# 004.net
KiCad netlist of a schematic drawn in EAGLE
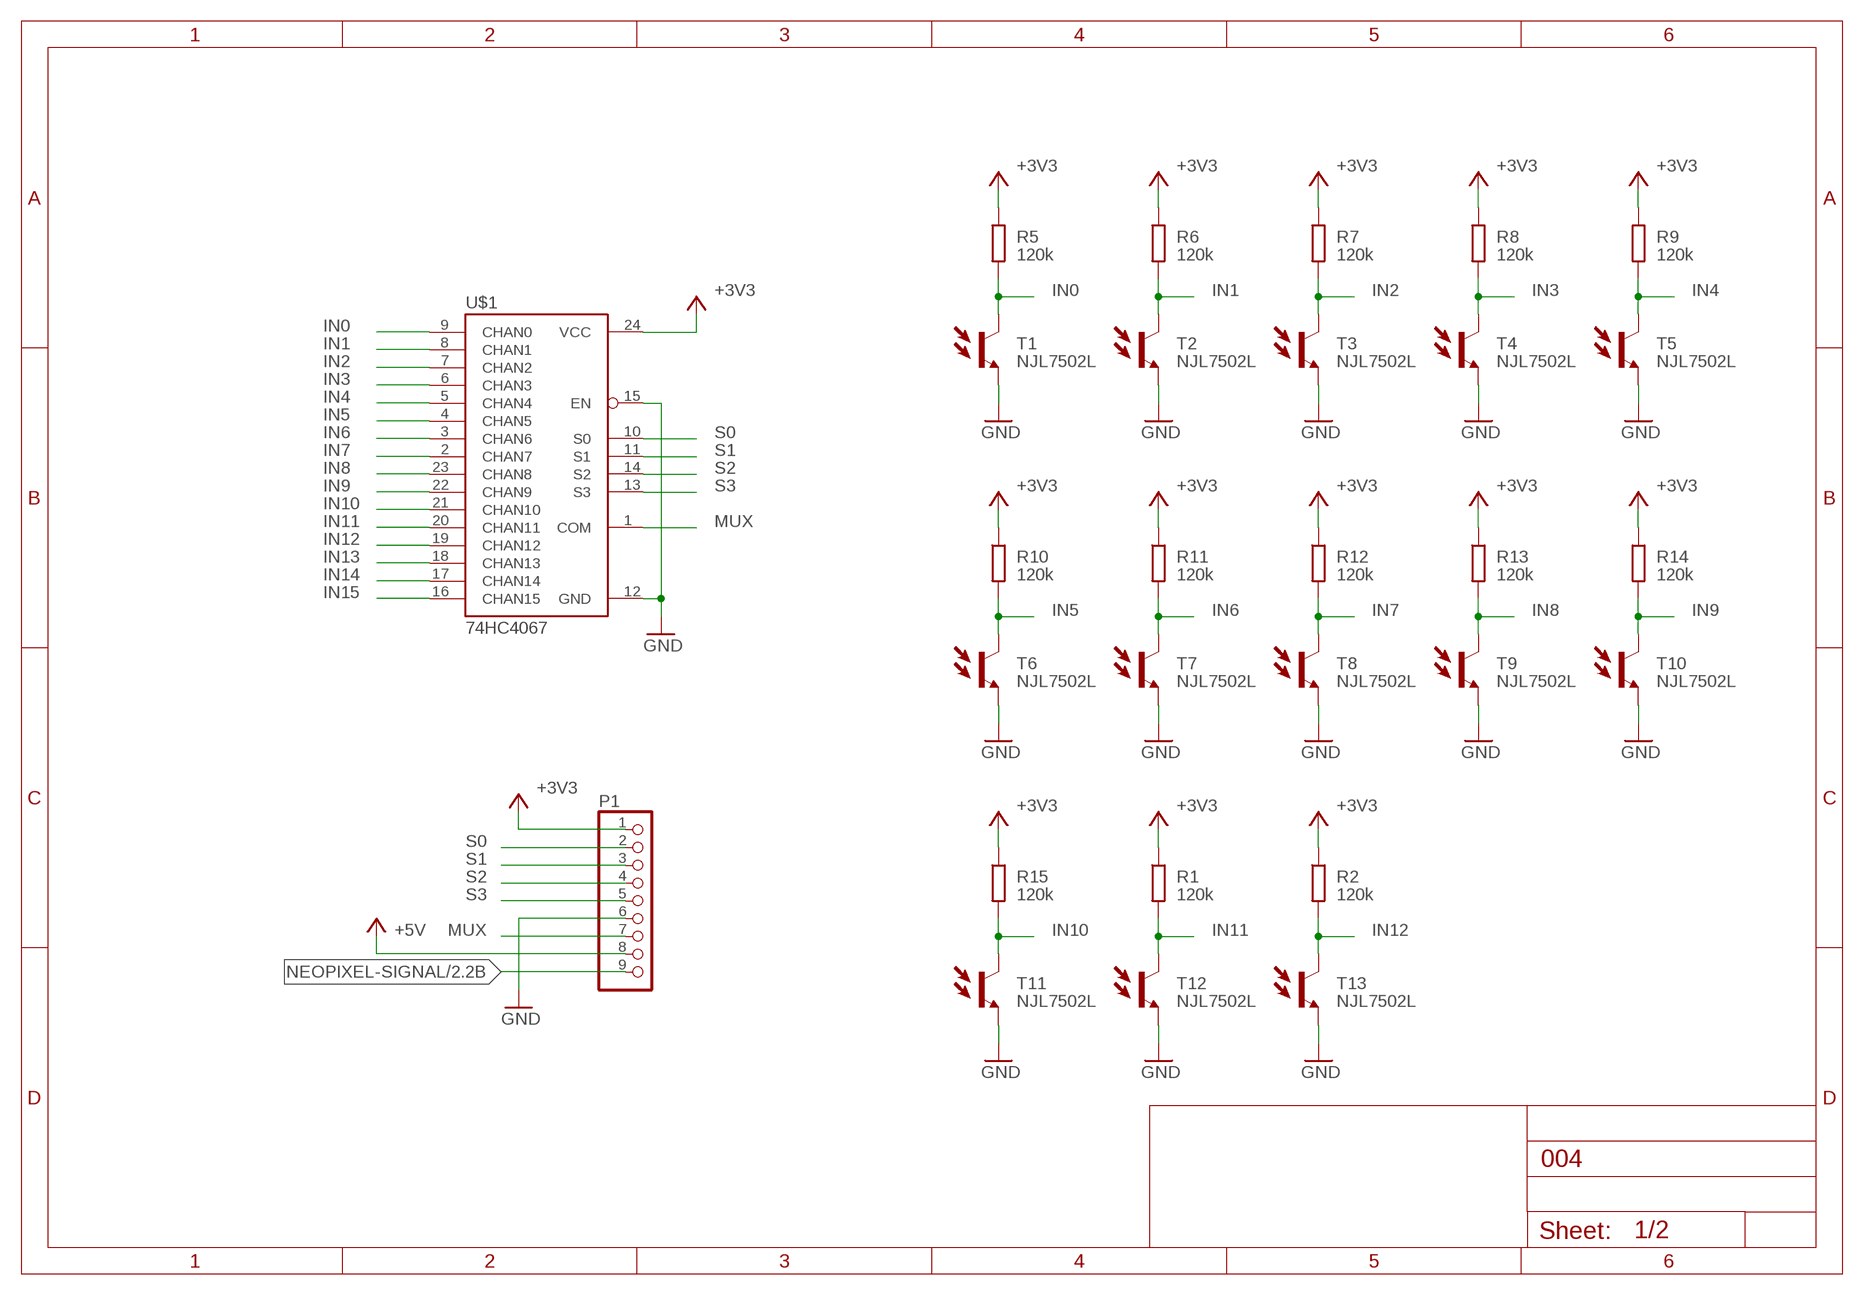
[diagram p0: schematic, sheet 1]
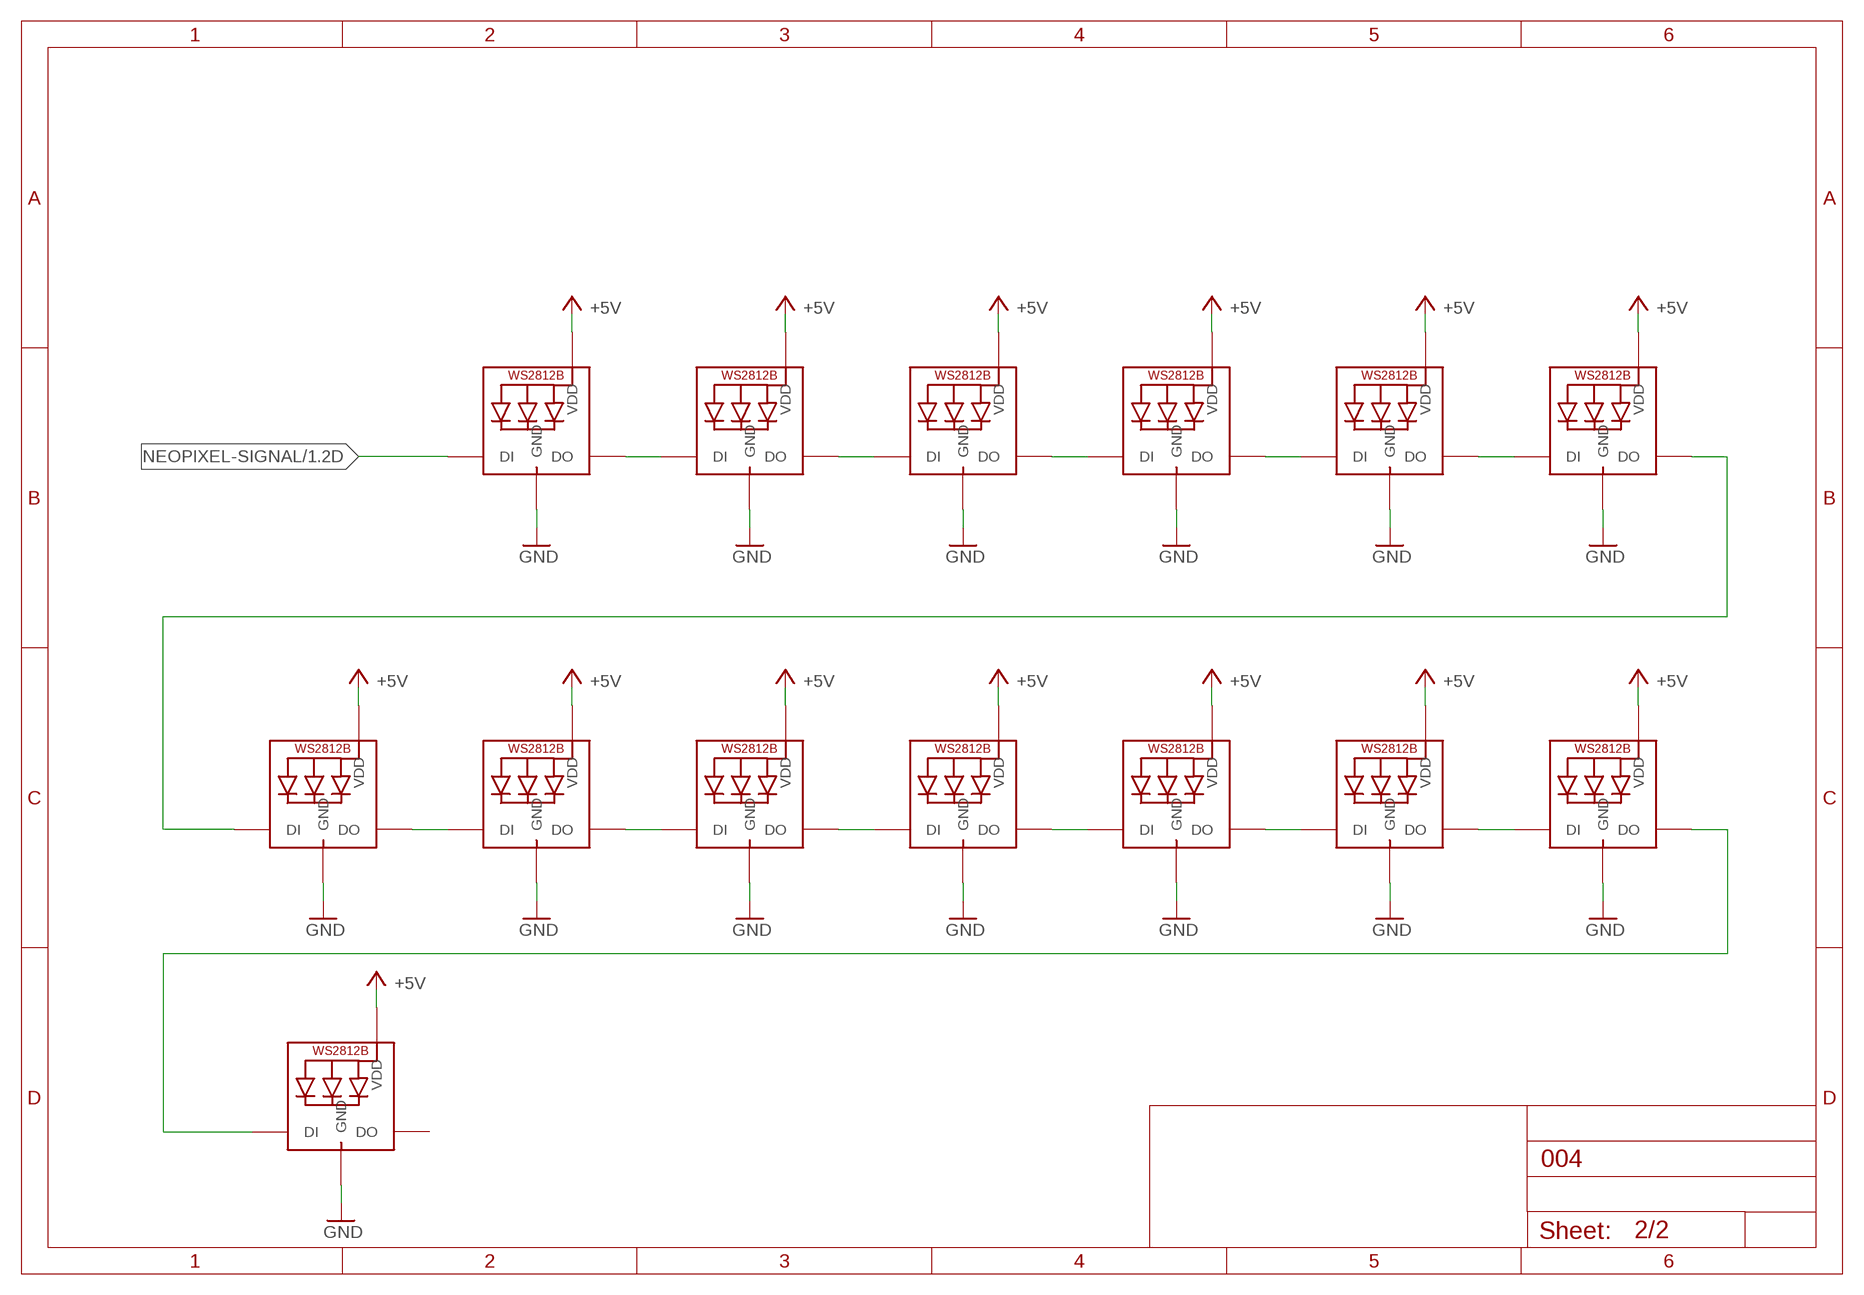
[diagram p1: schematic, sheet 2]

(export (version "E")
  (design (tool "Eeschema 10.0.6"))
  (components
    (comp (ref "P1")
      (value "S9B-ZR-SM4A-TF")
      (footprint "eagle-import:ZH-SM4-SIDE09")
      (libsource (lib "eagle-import") (part "S9B-ZR-SM4A-TF"))
    )
    (comp (ref "R1")
      (value "120k")
      (footprint "eagle-import:R0805")
      (libsource (lib "eagle-import") (part "R-EU_R0805"))
    )
    (comp (ref "R2")
      (value "120k")
      (footprint "eagle-import:R0805")
      (libsource (lib "eagle-import") (part "R-EU_R0805"))
    )
    (comp (ref "R5")
      (value "120k")
      (footprint "eagle-import:R0805")
      (libsource (lib "eagle-import") (part "R-EU_R0805"))
    )
    (comp (ref "R6")
      (value "120k")
      (footprint "eagle-import:R0805")
      (libsource (lib "eagle-import") (part "R-EU_R0805"))
    )
    (comp (ref "R7")
      (value "120k")
      (footprint "eagle-import:R0805")
      (libsource (lib "eagle-import") (part "R-EU_R0805"))
    )
    (comp (ref "R8")
      (value "120k")
      (footprint "eagle-import:R0805")
      (libsource (lib "eagle-import") (part "R-EU_R0805"))
    )
    (comp (ref "R9")
      (value "120k")
      (footprint "eagle-import:R0805")
      (libsource (lib "eagle-import") (part "R-EU_R0805"))
    )
    (comp (ref "R10")
      (value "120k")
      (footprint "eagle-import:R0805")
      (libsource (lib "eagle-import") (part "R-EU_R0805"))
    )
    (comp (ref "R11")
      (value "120k")
      (footprint "eagle-import:R0805")
      (libsource (lib "eagle-import") (part "R-EU_R0805"))
    )
    (comp (ref "R12")
      (value "120k")
      (footprint "eagle-import:R0805")
      (libsource (lib "eagle-import") (part "R-EU_R0805"))
    )
    (comp (ref "R13")
      (value "120k")
      (footprint "eagle-import:R0805")
      (libsource (lib "eagle-import") (part "R-EU_R0805"))
    )
    (comp (ref "R14")
      (value "120k")
      (footprint "eagle-import:R0805")
      (libsource (lib "eagle-import") (part "R-EU_R0805"))
    )
    (comp (ref "R15")
      (value "120k")
      (footprint "eagle-import:R0805")
      (libsource (lib "eagle-import") (part "R-EU_R0805"))
    )
    (comp (ref "T1")
      (value "NJL7502L")
      (footprint "eagle-import:MYPARTS_NJL7502L")
      (libsource (lib "eagle-import") (part "MYPARTS_NJL7502L"))
    )
    (comp (ref "T2")
      (value "NJL7502L")
      (footprint "eagle-import:MYPARTS_NJL7502L")
      (libsource (lib "eagle-import") (part "MYPARTS_NJL7502L"))
    )
    (comp (ref "T3")
      (value "NJL7502L")
      (footprint "eagle-import:MYPARTS_NJL7502L")
      (libsource (lib "eagle-import") (part "MYPARTS_NJL7502L"))
    )
    (comp (ref "T4")
      (value "NJL7502L")
      (footprint "eagle-import:MYPARTS_NJL7502L")
      (libsource (lib "eagle-import") (part "MYPARTS_NJL7502L"))
    )
    (comp (ref "T5")
      (value "NJL7502L")
      (footprint "eagle-import:MYPARTS_NJL7502L")
      (libsource (lib "eagle-import") (part "MYPARTS_NJL7502L"))
    )
    (comp (ref "T6")
      (value "NJL7502L")
      (footprint "eagle-import:MYPARTS_NJL7502L")
      (libsource (lib "eagle-import") (part "MYPARTS_NJL7502L"))
    )
    (comp (ref "T7")
      (value "NJL7502L")
      (footprint "eagle-import:MYPARTS_NJL7502L")
      (libsource (lib "eagle-import") (part "MYPARTS_NJL7502L"))
    )
    (comp (ref "T8")
      (value "NJL7502L")
      (footprint "eagle-import:MYPARTS_NJL7502L")
      (libsource (lib "eagle-import") (part "MYPARTS_NJL7502L"))
    )
    (comp (ref "T9")
      (value "NJL7502L")
      (footprint "eagle-import:MYPARTS_NJL7502L")
      (libsource (lib "eagle-import") (part "MYPARTS_NJL7502L"))
    )
    (comp (ref "T10")
      (value "NJL7502L")
      (footprint "eagle-import:MYPARTS_NJL7502L")
      (libsource (lib "eagle-import") (part "MYPARTS_NJL7502L"))
    )
    (comp (ref "T11")
      (value "NJL7502L")
      (footprint "eagle-import:MYPARTS_NJL7502L")
      (libsource (lib "eagle-import") (part "MYPARTS_NJL7502L"))
    )
    (comp (ref "T12")
      (value "NJL7502L")
      (footprint "eagle-import:MYPARTS_NJL7502L")
      (libsource (lib "eagle-import") (part "MYPARTS_NJL7502L"))
    )
    (comp (ref "T13")
      (value "NJL7502L")
      (footprint "eagle-import:MYPARTS_NJL7502L")
      (libsource (lib "eagle-import") (part "MYPARTS_NJL7502L"))
    )
    (comp (ref "U$1")
      (value "74HC4067")
      (footprint "eagle-import:SPARKFUN_SSOP24")
      (libsource (lib "eagle-import") (part "SPARKFUN_MUX-74HC4067SMD"))
    )
    (comp (ref "LED1")
      (value "WS2812B5050")
      (footprint "eagle-import:WS2812B")
      (libsource (lib "eagle-import") (part "WS2812B5050"))
    )
    (comp (ref "LED2")
      (value "WS2812B5050")
      (footprint "eagle-import:WS2812B")
      (libsource (lib "eagle-import") (part "WS2812B5050"))
    )
    (comp (ref "LED3")
      (value "WS2812B5050")
      (footprint "eagle-import:WS2812B")
      (libsource (lib "eagle-import") (part "WS2812B5050"))
    )
    (comp (ref "LED4")
      (value "WS2812B5050")
      (footprint "eagle-import:WS2812B")
      (libsource (lib "eagle-import") (part "WS2812B5050"))
    )
    (comp (ref "LED5")
      (value "WS2812B5050")
      (footprint "eagle-import:WS2812B")
      (libsource (lib "eagle-import") (part "WS2812B5050"))
    )
    (comp (ref "LED6")
      (value "WS2812B5050")
      (footprint "eagle-import:WS2812B")
      (libsource (lib "eagle-import") (part "WS2812B5050"))
    )
    (comp (ref "LED7")
      (value "WS2812B5050")
      (footprint "eagle-import:WS2812B")
      (libsource (lib "eagle-import") (part "WS2812B5050"))
    )
    (comp (ref "LED8")
      (value "WS2812B5050")
      (footprint "eagle-import:WS2812B")
      (libsource (lib "eagle-import") (part "WS2812B5050"))
    )
    (comp (ref "LED9")
      (value "WS2812B5050")
      (footprint "eagle-import:WS2812B")
      (libsource (lib "eagle-import") (part "WS2812B5050"))
    )
    (comp (ref "LED10")
      (value "WS2812B5050")
      (footprint "eagle-import:WS2812B")
      (libsource (lib "eagle-import") (part "WS2812B5050"))
    )
    (comp (ref "LED11")
      (value "WS2812B5050")
      (footprint "eagle-import:WS2812B")
      (libsource (lib "eagle-import") (part "WS2812B5050"))
    )
    (comp (ref "LED12")
      (value "WS2812B5050")
      (footprint "eagle-import:WS2812B")
      (libsource (lib "eagle-import") (part "WS2812B5050"))
    )
    (comp (ref "LED13")
      (value "WS2812B5050")
      (footprint "eagle-import:WS2812B")
      (libsource (lib "eagle-import") (part "WS2812B5050"))
    )
    (comp (ref "LED14")
      (value "WS2812B5050")
      (footprint "eagle-import:WS2812B")
      (libsource (lib "eagle-import") (part "WS2812B5050"))
    )
  )
  (nets
    (net (code "1") (name "+3V3") (class "Default")
      (node (ref "P1") (pin "1") (pinfunction "1_1") (pintype "passive"))
      (node (ref "R1") (pin "1") (pinfunction "1_1") (pintype "passive"))
      (node (ref "R10") (pin "1") (pinfunction "1_1") (pintype "passive"))
      (node (ref "R11") (pin "1") (pinfunction "1_1") (pintype "passive"))
      (node (ref "R12") (pin "1") (pinfunction "1_1") (pintype "passive"))
      (node (ref "R13") (pin "1") (pinfunction "1_1") (pintype "passive"))
      (node (ref "R14") (pin "1") (pinfunction "1_1") (pintype "passive"))
      (node (ref "R15") (pin "1") (pinfunction "1_1") (pintype "passive"))
      (node (ref "R2") (pin "1") (pinfunction "1_1") (pintype "passive"))
      (node (ref "R5") (pin "1") (pinfunction "1_1") (pintype "passive"))
      (node (ref "R6") (pin "1") (pinfunction "1_1") (pintype "passive"))
      (node (ref "R7") (pin "1") (pinfunction "1_1") (pintype "passive"))
      (node (ref "R8") (pin "1") (pinfunction "1_1") (pintype "passive"))
      (node (ref "R9") (pin "1") (pinfunction "1_1") (pintype "passive"))
      (node (ref "U$1") (pin "24") (pinfunction "VCC_24") (pintype "bidirectional"))
    )
    (net (code "2") (name "+5V") (class "Default")
      (node (ref "LED1") (pin "1-VDD") (pinfunction "VDD_1-VDD") (pintype "power_in"))
      (node (ref "LED10") (pin "1-VDD") (pinfunction "VDD_1-VDD") (pintype "power_in"))
      (node (ref "LED11") (pin "1-VDD") (pinfunction "VDD_1-VDD") (pintype "power_in"))
      (node (ref "LED12") (pin "1-VDD") (pinfunction "VDD_1-VDD") (pintype "power_in"))
      (node (ref "LED13") (pin "1-VDD") (pinfunction "VDD_1-VDD") (pintype "power_in"))
      (node (ref "LED14") (pin "1-VDD") (pinfunction "VDD_1-VDD") (pintype "power_in"))
      (node (ref "LED2") (pin "1-VDD") (pinfunction "VDD_1-VDD") (pintype "power_in"))
      (node (ref "LED3") (pin "1-VDD") (pinfunction "VDD_1-VDD") (pintype "power_in"))
      (node (ref "LED4") (pin "1-VDD") (pinfunction "VDD_1-VDD") (pintype "power_in"))
      (node (ref "LED5") (pin "1-VDD") (pinfunction "VDD_1-VDD") (pintype "power_in"))
      (node (ref "LED6") (pin "1-VDD") (pinfunction "VDD_1-VDD") (pintype "power_in"))
      (node (ref "LED7") (pin "1-VDD") (pinfunction "VDD_1-VDD") (pintype "power_in"))
      (node (ref "LED8") (pin "1-VDD") (pinfunction "VDD_1-VDD") (pintype "power_in"))
      (node (ref "LED9") (pin "1-VDD") (pinfunction "VDD_1-VDD") (pintype "power_in"))
      (node (ref "P1") (pin "8") (pinfunction "8_8") (pintype "passive"))
    )
    (net (code "3") (name "GND") (class "Default")
      (node (ref "LED1") (pin "3-GND") (pinfunction "GND_3-GND") (pintype "power_in"))
      (node (ref "LED10") (pin "3-GND") (pinfunction "GND_3-GND") (pintype "power_in"))
      (node (ref "LED11") (pin "3-GND") (pinfunction "GND_3-GND") (pintype "power_in"))
      (node (ref "LED12") (pin "3-GND") (pinfunction "GND_3-GND") (pintype "power_in"))
      (node (ref "LED13") (pin "3-GND") (pinfunction "GND_3-GND") (pintype "power_in"))
      (node (ref "LED14") (pin "3-GND") (pinfunction "GND_3-GND") (pintype "power_in"))
      (node (ref "LED2") (pin "3-GND") (pinfunction "GND_3-GND") (pintype "power_in"))
      (node (ref "LED3") (pin "3-GND") (pinfunction "GND_3-GND") (pintype "power_in"))
      (node (ref "LED4") (pin "3-GND") (pinfunction "GND_3-GND") (pintype "power_in"))
      (node (ref "LED5") (pin "3-GND") (pinfunction "GND_3-GND") (pintype "power_in"))
      (node (ref "LED6") (pin "3-GND") (pinfunction "GND_3-GND") (pintype "power_in"))
      (node (ref "LED7") (pin "3-GND") (pinfunction "GND_3-GND") (pintype "power_in"))
      (node (ref "LED8") (pin "3-GND") (pinfunction "GND_3-GND") (pintype "power_in"))
      (node (ref "LED9") (pin "3-GND") (pinfunction "GND_3-GND") (pintype "power_in"))
      (node (ref "P1") (pin "6") (pinfunction "6_6") (pintype "passive"))
      (node (ref "T1") (pin "E") (pinfunction "E_E") (pintype "passive"))
      (node (ref "T10") (pin "E") (pinfunction "E_E") (pintype "passive"))
      (node (ref "T11") (pin "E") (pinfunction "E_E") (pintype "passive"))
      (node (ref "T12") (pin "E") (pinfunction "E_E") (pintype "passive"))
      (node (ref "T13") (pin "E") (pinfunction "E_E") (pintype "passive"))
      (node (ref "T2") (pin "E") (pinfunction "E_E") (pintype "passive"))
      (node (ref "T3") (pin "E") (pinfunction "E_E") (pintype "passive"))
      (node (ref "T4") (pin "E") (pinfunction "E_E") (pintype "passive"))
      (node (ref "T5") (pin "E") (pinfunction "E_E") (pintype "passive"))
      (node (ref "T6") (pin "E") (pinfunction "E_E") (pintype "passive"))
      (node (ref "T7") (pin "E") (pinfunction "E_E") (pintype "passive"))
      (node (ref "T8") (pin "E") (pinfunction "E_E") (pintype "passive"))
      (node (ref "T9") (pin "E") (pinfunction "E_E") (pintype "passive"))
      (node (ref "U$1") (pin "12") (pinfunction "GND_12") (pintype "bidirectional"))
      (node (ref "U$1") (pin "15") (pinfunction "EN_15") (pintype "input"))
    )
    (net (code "4") (name "IN0") (class "Default")
      (node (ref "R5") (pin "2") (pinfunction "2_2") (pintype "passive"))
      (node (ref "T1") (pin "C") (pinfunction "C_C") (pintype "passive"))
      (node (ref "U$1") (pin "9") (pinfunction "CHAN0_9") (pintype "bidirectional"))
    )
    (net (code "5") (name "IN1") (class "Default")
      (node (ref "R6") (pin "2") (pinfunction "2_2") (pintype "passive"))
      (node (ref "T2") (pin "C") (pinfunction "C_C") (pintype "passive"))
      (node (ref "U$1") (pin "8") (pinfunction "CHAN1_8") (pintype "bidirectional"))
    )
    (net (code "6") (name "IN2") (class "Default")
      (node (ref "R7") (pin "2") (pinfunction "2_2") (pintype "passive"))
      (node (ref "T3") (pin "C") (pinfunction "C_C") (pintype "passive"))
      (node (ref "U$1") (pin "7") (pinfunction "CHAN2_7") (pintype "bidirectional"))
    )
    (net (code "7") (name "IN3") (class "Default")
      (node (ref "R8") (pin "2") (pinfunction "2_2") (pintype "passive"))
      (node (ref "T4") (pin "C") (pinfunction "C_C") (pintype "passive"))
      (node (ref "U$1") (pin "6") (pinfunction "CHAN3_6") (pintype "bidirectional"))
    )
    (net (code "8") (name "IN4") (class "Default")
      (node (ref "R9") (pin "2") (pinfunction "2_2") (pintype "passive"))
      (node (ref "T5") (pin "C") (pinfunction "C_C") (pintype "passive"))
      (node (ref "U$1") (pin "5") (pinfunction "CHAN4_5") (pintype "bidirectional"))
    )
    (net (code "9") (name "IN5") (class "Default")
      (node (ref "R10") (pin "2") (pinfunction "2_2") (pintype "passive"))
      (node (ref "T6") (pin "C") (pinfunction "C_C") (pintype "passive"))
      (node (ref "U$1") (pin "4") (pinfunction "CHAN5_4") (pintype "bidirectional"))
    )
    (net (code "10") (name "IN6") (class "Default")
      (node (ref "R11") (pin "2") (pinfunction "2_2") (pintype "passive"))
      (node (ref "T7") (pin "C") (pinfunction "C_C") (pintype "passive"))
      (node (ref "U$1") (pin "3") (pinfunction "CHAN6_3") (pintype "bidirectional"))
    )
    (net (code "11") (name "IN7") (class "Default")
      (node (ref "R12") (pin "2") (pinfunction "2_2") (pintype "passive"))
      (node (ref "T8") (pin "C") (pinfunction "C_C") (pintype "passive"))
      (node (ref "U$1") (pin "2") (pinfunction "CHAN7_2") (pintype "bidirectional"))
    )
    (net (code "12") (name "IN8") (class "Default")
      (node (ref "R13") (pin "2") (pinfunction "2_2") (pintype "passive"))
      (node (ref "T9") (pin "C") (pinfunction "C_C") (pintype "passive"))
      (node (ref "U$1") (pin "23") (pinfunction "CHAN8_23") (pintype "bidirectional"))
    )
    (net (code "13") (name "IN9") (class "Default")
      (node (ref "R14") (pin "2") (pinfunction "2_2") (pintype "passive"))
      (node (ref "T10") (pin "C") (pinfunction "C_C") (pintype "passive"))
      (node (ref "U$1") (pin "22") (pinfunction "CHAN9_22") (pintype "bidirectional"))
    )
    (net (code "14") (name "IN10") (class "Default")
      (node (ref "R15") (pin "2") (pinfunction "2_2") (pintype "passive"))
      (node (ref "T11") (pin "C") (pinfunction "C_C") (pintype "passive"))
      (node (ref "U$1") (pin "21") (pinfunction "CHAN10_21") (pintype "bidirectional"))
    )
    (net (code "15") (name "IN11") (class "Default")
      (node (ref "R1") (pin "2") (pinfunction "2_2") (pintype "passive"))
      (node (ref "T12") (pin "C") (pinfunction "C_C") (pintype "passive"))
      (node (ref "U$1") (pin "20") (pinfunction "CHAN11_20") (pintype "bidirectional"))
    )
    (net (code "16") (name "IN12") (class "Default")
      (node (ref "R2") (pin "2") (pinfunction "2_2") (pintype "passive"))
      (node (ref "T13") (pin "C") (pinfunction "C_C") (pintype "passive"))
      (node (ref "U$1") (pin "19") (pinfunction "CHAN12_19") (pintype "bidirectional"))
    )
    (net (code "17") (name "IN13") (class "Default")
      (node (ref "U$1") (pin "18") (pinfunction "CHAN13_18") (pintype "bidirectional"))
    )
    (net (code "18") (name "IN14") (class "Default")
      (node (ref "U$1") (pin "17") (pinfunction "CHAN14_17") (pintype "bidirectional"))
    )
    (net (code "19") (name "IN15") (class "Default")
      (node (ref "U$1") (pin "16") (pinfunction "CHAN15_16") (pintype "bidirectional"))
    )
    (net (code "20") (name "MUX") (class "Default")
      (node (ref "P1") (pin "7") (pinfunction "7_7") (pintype "passive"))
      (node (ref "U$1") (pin "1") (pinfunction "COM_1") (pintype "bidirectional"))
    )
    (net (code "21") (name "NEOPIXEL-SIGNAL") (class "Default")
      (node (ref "LED1") (pin "4-DIN") (pinfunction "DI_4-DIN") (pintype "input"))
      (node (ref "P1") (pin "9") (pinfunction "9_9") (pintype "passive"))
    )
    (net (code "22") (name "Net-(LED1-DO)") (class "Default")
      (node (ref "LED1") (pin "2-DOUT") (pinfunction "DO_2-DOUT") (pintype "output"))
      (node (ref "LED2") (pin "4-DIN") (pinfunction "DI_4-DIN") (pintype "input"))
    )
    (net (code "23") (name "Net-(LED2-DO)") (class "Default")
      (node (ref "LED2") (pin "2-DOUT") (pinfunction "DO_2-DOUT") (pintype "output"))
      (node (ref "LED3") (pin "4-DIN") (pinfunction "DI_4-DIN") (pintype "input"))
    )
    (net (code "24") (name "Net-(LED3-DO)") (class "Default")
      (node (ref "LED3") (pin "2-DOUT") (pinfunction "DO_2-DOUT") (pintype "output"))
      (node (ref "LED4") (pin "4-DIN") (pinfunction "DI_4-DIN") (pintype "input"))
    )
    (net (code "25") (name "Net-(LED4-DO)") (class "Default")
      (node (ref "LED4") (pin "2-DOUT") (pinfunction "DO_2-DOUT") (pintype "output"))
      (node (ref "LED5") (pin "4-DIN") (pinfunction "DI_4-DIN") (pintype "input"))
    )
    (net (code "26") (name "Net-(LED5-DO)") (class "Default")
      (node (ref "LED5") (pin "2-DOUT") (pinfunction "DO_2-DOUT") (pintype "output"))
      (node (ref "LED6") (pin "4-DIN") (pinfunction "DI_4-DIN") (pintype "input"))
    )
    (net (code "27") (name "Net-(LED6-DO)") (class "Default")
      (node (ref "LED6") (pin "2-DOUT") (pinfunction "DO_2-DOUT") (pintype "output"))
      (node (ref "LED7") (pin "4-DIN") (pinfunction "DI_4-DIN") (pintype "input"))
    )
    (net (code "28") (name "Net-(LED7-DO)") (class "Default")
      (node (ref "LED7") (pin "2-DOUT") (pinfunction "DO_2-DOUT") (pintype "output"))
      (node (ref "LED8") (pin "4-DIN") (pinfunction "DI_4-DIN") (pintype "input"))
    )
    (net (code "29") (name "Net-(LED8-DO)") (class "Default")
      (node (ref "LED8") (pin "2-DOUT") (pinfunction "DO_2-DOUT") (pintype "output"))
      (node (ref "LED9") (pin "4-DIN") (pinfunction "DI_4-DIN") (pintype "input"))
    )
    (net (code "30") (name "Net-(LED10-DI)") (class "Default")
      (node (ref "LED10") (pin "4-DIN") (pinfunction "DI_4-DIN") (pintype "input"))
      (node (ref "LED9") (pin "2-DOUT") (pinfunction "DO_2-DOUT") (pintype "output"))
    )
    (net (code "31") (name "Net-(LED10-DO)") (class "Default")
      (node (ref "LED10") (pin "2-DOUT") (pinfunction "DO_2-DOUT") (pintype "output"))
      (node (ref "LED11") (pin "4-DIN") (pinfunction "DI_4-DIN") (pintype "input"))
    )
    (net (code "32") (name "Net-(LED11-DO)") (class "Default")
      (node (ref "LED11") (pin "2-DOUT") (pinfunction "DO_2-DOUT") (pintype "output"))
      (node (ref "LED12") (pin "4-DIN") (pinfunction "DI_4-DIN") (pintype "input"))
    )
    (net (code "33") (name "Net-(LED12-DO)") (class "Default")
      (node (ref "LED12") (pin "2-DOUT") (pinfunction "DO_2-DOUT") (pintype "output"))
      (node (ref "LED13") (pin "4-DIN") (pinfunction "DI_4-DIN") (pintype "input"))
    )
    (net (code "34") (name "Net-(LED13-DO)") (class "Default")
      (node (ref "LED13") (pin "2-DOUT") (pinfunction "DO_2-DOUT") (pintype "output"))
      (node (ref "LED14") (pin "4-DIN") (pinfunction "DI_4-DIN") (pintype "input"))
    )
    (net (code "35") (name "S0") (class "Default")
      (node (ref "P1") (pin "2") (pinfunction "2_2") (pintype "passive"))
      (node (ref "U$1") (pin "10") (pinfunction "S0_10") (pintype "input"))
    )
    (net (code "36") (name "S1") (class "Default")
      (node (ref "P1") (pin "3") (pinfunction "3_3") (pintype "passive"))
      (node (ref "U$1") (pin "11") (pinfunction "S1_11") (pintype "input"))
    )
    (net (code "37") (name "S2") (class "Default")
      (node (ref "P1") (pin "4") (pinfunction "4_4") (pintype "passive"))
      (node (ref "U$1") (pin "14") (pinfunction "S2_14") (pintype "input"))
    )
    (net (code "38") (name "S3") (class "Default")
      (node (ref "P1") (pin "5") (pinfunction "5_5") (pintype "passive"))
      (node (ref "U$1") (pin "13") (pinfunction "S3_13") (pintype "input"))
    )
    (net (code "39") (name "unconnected-(LED14-DO-Pad2-DOUT)") (class "Default")
      (node (ref "LED14") (pin "2-DOUT") (pinfunction "DO_2-DOUT") (pintype "output"))
    )
  )
)
